# design.net
KiCad netlist of a schematic drawn in EasyEDA Pro
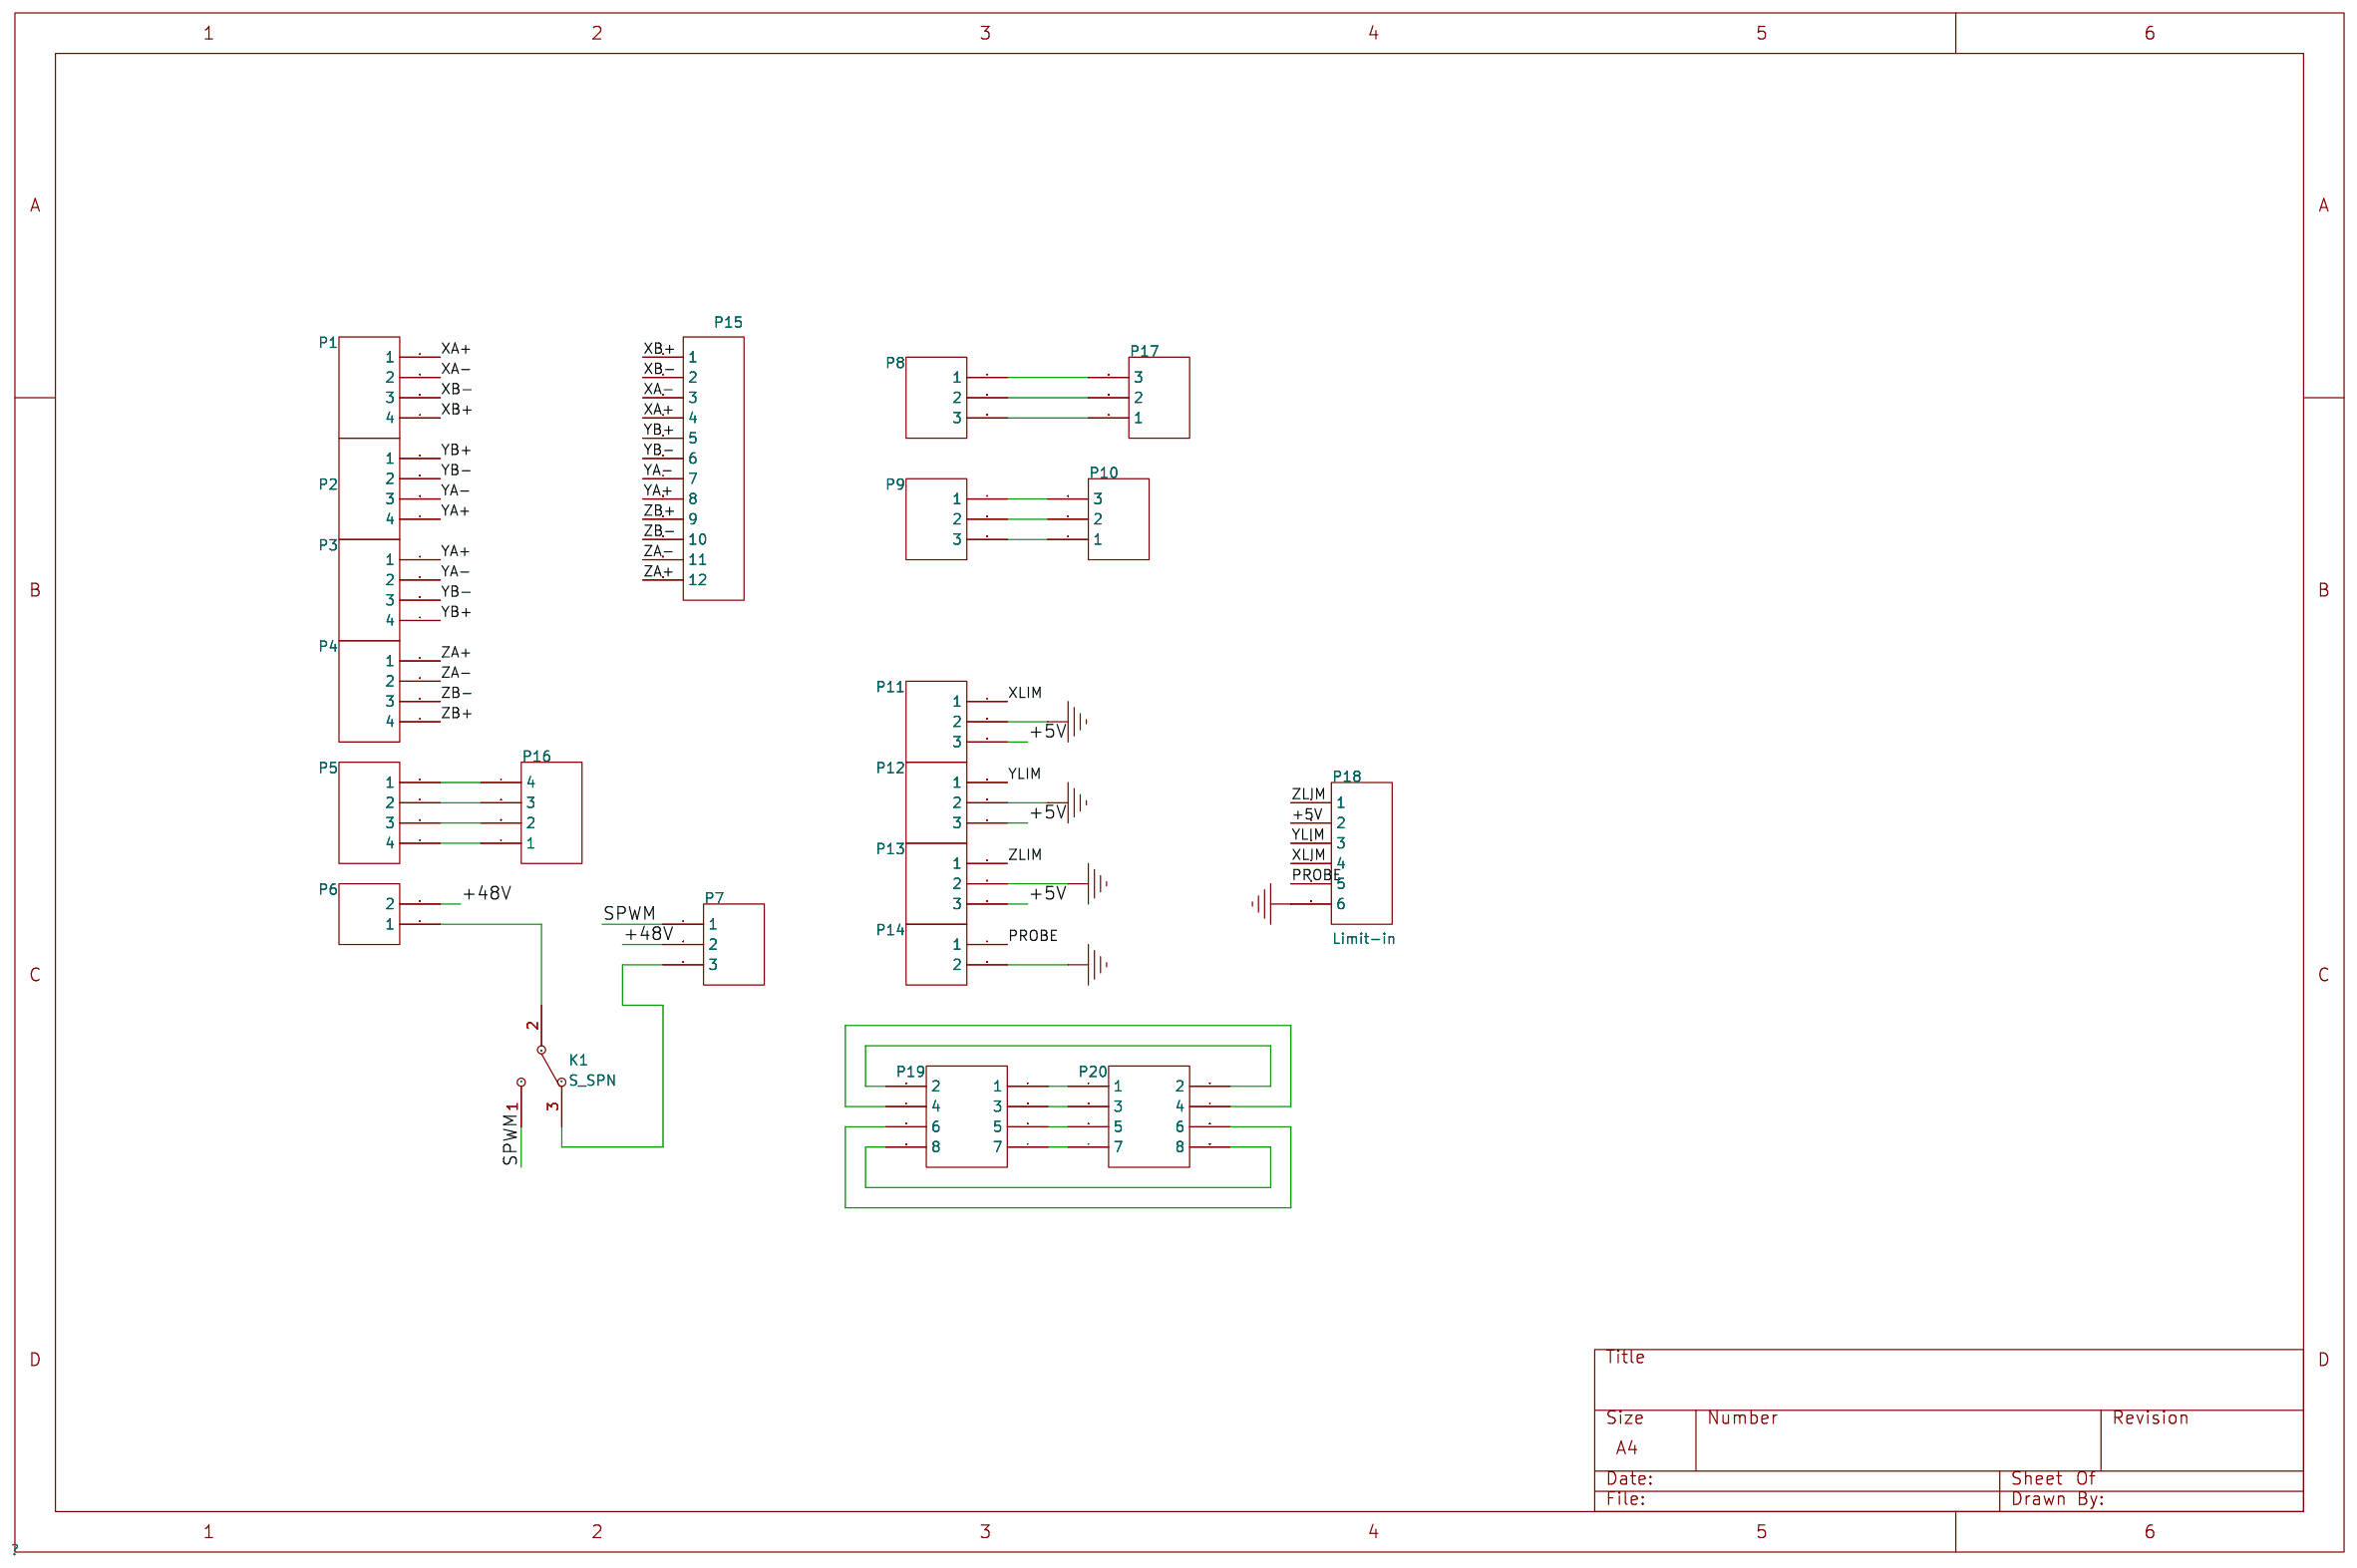
[diagram p0: schematic sheet]

(export (version "E")
  (design (tool "Eeschema 10.0.6"))
  (components
    (comp (ref "K1")
      (value "S_SPN")
      (footprint "easyedapro:SW-TH_SS-12D10L3")
      (description "SS-12D10L5")
      (fields (field (name "Publisher") "Altium Limited"))
      (libsource (lib "easyedapro") (part "SW-SPDT"))
    )
    (comp (ref "P1")
      (value "X-out")
      (footprint "easyedapro:HDR1X4_CON")
      (description "KF2EDGVC-5.0-4P，直插")
      (fields (field (name "Publisher") "Altium Limited"))
      (libsource (lib "easyedapro") (part "Header 4H"))
    )
    (comp (ref "P2")
      (value "Y1-out")
      (footprint "easyedapro:HDR1X4_CON")
      (description "KF2EDGVC-5.0-4P，直插")
      (fields (field (name "Publisher") "Altium Limited"))
      (libsource (lib "easyedapro") (part "Header 4H"))
    )
    (comp (ref "P3")
      (value "Y2-out")
      (footprint "easyedapro:HDR1X4_CON")
      (description "KF2EDGVC-5.0-4P，直插")
      (fields (field (name "Publisher") "Altium Limited"))
      (libsource (lib "easyedapro") (part "Header 4H"))
    )
    (comp (ref "P4")
      (value "Z-out")
      (footprint "easyedapro:HDR1X4_CON")
      (description "KF2EDGVC-5.0-4P，直插")
      (fields (field (name "Publisher") "Altium Limited"))
      (libsource (lib "easyedapro") (part "Header 4H"))
    )
    (comp (ref "P5")
      (value "Aout")
      (footprint "easyedapro:HDR1X4_CON")
      (description "KF2EDGVC-5.0-4P，直插")
      (fields (field (name "Publisher") "Altium Limited"))
      (libsource (lib "easyedapro") (part "Header 4H"))
    )
    (comp (ref "P6")
      (value "SPN-out")
      (footprint "easyedapro:CONN-TH_2P-P5.00_KF2EDGVC-5.08-2P")
      (description "KF2EDGVC-5.0-2P，直插")
      (fields (field (name "Publisher") "Altium Limited"))
      (libsource (lib "easyedapro") (part "Header 2H"))
    )
    (comp (ref "P7")
      (value "SPN-in")
      (footprint "easyedapro:CONN-TH_3P-P5.00_KF2EDGVC-5.08-3P")
      (description "KF2EDGVC-5.0-3P，直插")
      (fields (field (name "Publisher") "Altium Limited"))
      (libsource (lib "easyedapro") (part "Header 3H"))
    )
    (comp (ref "P8")
      (value "Laser-out")
      (footprint "easyedapro:CONN-TH_3P-P5.00_KF2EDGVC-5.08-3P")
      (description "KF2EDGVC-5.0-3P，直插")
      (fields (field (name "Publisher") "Altium Limited"))
      (libsource (lib "easyedapro") (part "Header 3H"))
    )
    (comp (ref "P9")
      (value "BL-out")
      (footprint "easyedapro:CONN-TH_3P-P5.00_KF2EDGVC-5.08-3P")
      (description "KF2EDGVC-5.0-3P，直插")
      (fields (field (name "Publisher") "Altium Limited"))
      (libsource (lib "easyedapro") (part "Header 3H"))
    )
    (comp (ref "P10")
      (value "BL-in")
      (footprint "easyedapro:CONN-TH_3P-P5.00_KF2EDGVC-5.08-3P")
      (description "KF2EDGVC-5.0-3P，直插")
      (fields (field (name "Publisher") "Altium Limited"))
      (libsource (lib "easyedapro") (part "Header 3H"))
    )
    (comp (ref "P11")
      (value "XLimt-out")
      (footprint "easyedapro:CONN-TH_3P-P5.00_KF2EDGVC-5.08-3P")
      (description "KF2EDGVC-5.0-3P，直插")
      (fields (field (name "Publisher") "Altium Limited"))
      (libsource (lib "easyedapro") (part "Header 3H"))
    )
    (comp (ref "P12")
      (value "YLimt-out")
      (footprint "easyedapro:CONN-TH_3P-P5.00_KF2EDGVC-5.08-3P")
      (description "KF2EDGVC-5.0-3P，直插")
      (fields (field (name "Publisher") "Altium Limited"))
      (libsource (lib "easyedapro") (part "Header 3H"))
    )
    (comp (ref "P13")
      (value "ZLimt-out")
      (footprint "easyedapro:CONN-TH_3P-P5.00_KF2EDGVC-5.08-3P")
      (description "KF2EDGVC-5.0-3P，直插")
      (fields (field (name "Publisher") "Altium Limited"))
      (libsource (lib "easyedapro") (part "Header 3H"))
    )
    (comp (ref "P14")
      (value "Probe-out")
      (footprint "easyedapro:CONN-TH_2P-P5.00_KF2EDGVC-5.08-2P")
      (description "Header, 2-Pin, Right Angle")
      (fields (field (name "Publisher") "Altium Limited"))
      (libsource (lib "easyedapro") (part "Header 2H"))
    )
    (comp (ref "P15")
      (value "XYZAxis")
      (footprint "easyedapro:HDR1X12_CON")
      (description "2.54立式直插12P")
      (fields (field (name "Publisher") "Altium Limited"))
      (libsource (lib "easyedapro") (part "Header 12H"))
    )
    (comp (ref "P16")
      (value "Ain")
      (footprint "easyedapro:HDR1X4_CON")
      (description "2.54立式直插4P")
      (fields (field (name "Publisher") "Altium Limited"))
      (libsource (lib "easyedapro") (part "Header 4H"))
    )
    (comp (ref "P17")
      (value "Laser-in")
      (footprint "easyedapro:CONN-TH_3P-P5.00_KF2EDGVC-5.08-3P")
      (description "2.54立式直插3P")
      (fields (field (name "Publisher") "Altium Limited"))
      (libsource (lib "easyedapro") (part "Header 3H"))
    )
    (comp (ref "P18")
      (value "Limit-in")
      (footprint "easyedapro:HDR1X6_CON")
      (description "2.54立式直插6P")
      (fields (field (name "Publisher") "Altium Limited"))
      (libsource (lib "easyedapro") (part "Header 6"))
    )
    (comp (ref "P19")
      (value "Offline-out")
      (footprint "easyedapro:IDC-TH_MTB110-08S - duplicate")
      (description "IDC连接器（牛角/简牛）2x4P")
      (fields (field (name "Publisher") "Altium Limited"))
      (libsource (lib "easyedapro") (part "MHDR2X4"))
    )
    (comp (ref "P20")
      (value "Offline-in")
      (footprint "easyedapro:IDC-TH_MTB110-08S - duplicate")
      (description "IDC连接器（牛角/简牛）2x4P")
      (fields (field (name "Publisher") "Altium Limited"))
      (libsource (lib "easyedapro") (part "MHDR2X4"))
    )
  )
  (nets
    (net (code "1") (name "/+5V") (class "Default")
      (node (ref "P11") (pin "3") (pinfunction "3_3") (pintype "unspecified"))
      (node (ref "P12") (pin "3") (pinfunction "3_3") (pintype "unspecified"))
      (node (ref "P13") (pin "3") (pinfunction "3_3") (pintype "unspecified"))
      (node (ref "P18") (pin "2") (pinfunction "2_2") (pintype "unspecified"))
    )
    (net (code "2") (name "/+48V") (class "Default")
      (node (ref "P6") (pin "2") (pinfunction "2_2") (pintype "unspecified"))
      (node (ref "P7") (pin "2") (pinfunction "2_2") (pintype "unspecified"))
    )
    (net (code "3") (name "/PROBE") (class "Default")
      (node (ref "P14") (pin "1") (pinfunction "1_1") (pintype "unspecified"))
      (node (ref "P18") (pin "5") (pinfunction "5_5") (pintype "unspecified"))
    )
    (net (code "4") (name "/SPWM") (class "Default")
      (node (ref "K1") (pin "1") (pinfunction "1_1") (pintype "unspecified"))
      (node (ref "P7") (pin "1") (pinfunction "1_1") (pintype "unspecified"))
    )
    (net (code "5") (name "/XA+") (class "Default")
      (node (ref "P1") (pin "1") (pinfunction "1_1") (pintype "unspecified"))
      (node (ref "P15") (pin "4") (pinfunction "4_4") (pintype "unspecified"))
    )
    (net (code "6") (name "/XA-") (class "Default")
      (node (ref "P1") (pin "2") (pinfunction "2_2") (pintype "unspecified"))
      (node (ref "P15") (pin "3") (pinfunction "3_3") (pintype "unspecified"))
    )
    (net (code "7") (name "/XB+") (class "Default")
      (node (ref "P1") (pin "4") (pinfunction "4_4") (pintype "unspecified"))
      (node (ref "P15") (pin "1") (pinfunction "1_1") (pintype "unspecified"))
    )
    (net (code "8") (name "/XB-") (class "Default")
      (node (ref "P1") (pin "3") (pinfunction "3_3") (pintype "unspecified"))
      (node (ref "P15") (pin "2") (pinfunction "2_2") (pintype "unspecified"))
    )
    (net (code "9") (name "/XLIM") (class "Default")
      (node (ref "P11") (pin "1") (pinfunction "1_1") (pintype "unspecified"))
      (node (ref "P18") (pin "4") (pinfunction "4_4") (pintype "unspecified"))
    )
    (net (code "10") (name "/YA+") (class "Default")
      (node (ref "P15") (pin "8") (pinfunction "8_8") (pintype "unspecified"))
      (node (ref "P2") (pin "4") (pinfunction "4_4") (pintype "unspecified"))
      (node (ref "P3") (pin "1") (pinfunction "1_1") (pintype "unspecified"))
    )
    (net (code "11") (name "/YA-") (class "Default")
      (node (ref "P15") (pin "7") (pinfunction "7_7") (pintype "unspecified"))
      (node (ref "P2") (pin "3") (pinfunction "3_3") (pintype "unspecified"))
      (node (ref "P3") (pin "2") (pinfunction "2_2") (pintype "unspecified"))
    )
    (net (code "12") (name "/YB+") (class "Default")
      (node (ref "P15") (pin "5") (pinfunction "5_5") (pintype "unspecified"))
      (node (ref "P2") (pin "1") (pinfunction "1_1") (pintype "unspecified"))
      (node (ref "P3") (pin "4") (pinfunction "4_4") (pintype "unspecified"))
    )
    (net (code "13") (name "/YB-") (class "Default")
      (node (ref "P15") (pin "6") (pinfunction "6_6") (pintype "unspecified"))
      (node (ref "P2") (pin "2") (pinfunction "2_2") (pintype "unspecified"))
      (node (ref "P3") (pin "3") (pinfunction "3_3") (pintype "unspecified"))
    )
    (net (code "14") (name "/YLIM") (class "Default")
      (node (ref "P12") (pin "1") (pinfunction "1_1") (pintype "unspecified"))
      (node (ref "P18") (pin "3") (pinfunction "3_3") (pintype "unspecified"))
    )
    (net (code "15") (name "/ZA+") (class "Default")
      (node (ref "P15") (pin "12") (pinfunction "12_12") (pintype "unspecified"))
      (node (ref "P4") (pin "1") (pinfunction "1_1") (pintype "unspecified"))
    )
    (net (code "16") (name "/ZA-") (class "Default")
      (node (ref "P15") (pin "11") (pinfunction "11_11") (pintype "unspecified"))
      (node (ref "P4") (pin "2") (pinfunction "2_2") (pintype "unspecified"))
    )
    (net (code "17") (name "/ZB+") (class "Default")
      (node (ref "P15") (pin "9") (pinfunction "9_9") (pintype "unspecified"))
      (node (ref "P4") (pin "4") (pinfunction "4_4") (pintype "unspecified"))
    )
    (net (code "18") (name "/ZB-") (class "Default")
      (node (ref "P15") (pin "10") (pinfunction "10_10") (pintype "unspecified"))
      (node (ref "P4") (pin "3") (pinfunction "3_3") (pintype "unspecified"))
    )
    (net (code "19") (name "/ZLIM") (class "Default")
      (node (ref "P13") (pin "1") (pinfunction "1_1") (pintype "unspecified"))
      (node (ref "P18") (pin "1") (pinfunction "1_1") (pintype "unspecified"))
    )
    (net (code "20") (name "GND") (class "Default")
      (node (ref "P11") (pin "2") (pinfunction "2_2") (pintype "unspecified"))
      (node (ref "P12") (pin "2") (pinfunction "2_2") (pintype "unspecified"))
      (node (ref "P13") (pin "2") (pinfunction "2_2") (pintype "unspecified"))
      (node (ref "P14") (pin "2") (pinfunction "2_2") (pintype "unspecified"))
      (node (ref "P18") (pin "6") (pinfunction "6_6") (pintype "unspecified"))
    )
    (net (code "21") (name "Net-(K1-Pad2)") (class "Default")
      (node (ref "K1") (pin "2") (pinfunction "2_2") (pintype "unspecified"))
      (node (ref "P6") (pin "1") (pinfunction "1_1") (pintype "unspecified"))
    )
    (net (code "22") (name "Net-(K1-Pad3)") (class "Default")
      (node (ref "K1") (pin "3") (pinfunction "3_3") (pintype "unspecified"))
      (node (ref "P7") (pin "3") (pinfunction "3_3") (pintype "unspecified"))
    )
    (net (code "23") (name "Net-(P10-Pad1)") (class "Default")
      (node (ref "P10") (pin "1") (pinfunction "1_1") (pintype "unspecified"))
      (node (ref "P9") (pin "3") (pinfunction "3_3") (pintype "unspecified"))
    )
    (net (code "24") (name "Net-(P10-Pad2)") (class "Default")
      (node (ref "P10") (pin "2") (pinfunction "2_2") (pintype "unspecified"))
      (node (ref "P9") (pin "2") (pinfunction "2_2") (pintype "unspecified"))
    )
    (net (code "25") (name "Net-(P10-Pad3)") (class "Default")
      (node (ref "P10") (pin "3") (pinfunction "3_3") (pintype "unspecified"))
      (node (ref "P9") (pin "1") (pinfunction "1_1") (pintype "unspecified"))
    )
    (net (code "26") (name "Net-(P16-Pad1)") (class "Default")
      (node (ref "P16") (pin "1") (pinfunction "1_1") (pintype "unspecified"))
      (node (ref "P5") (pin "4") (pinfunction "4_4") (pintype "unspecified"))
    )
    (net (code "27") (name "Net-(P16-Pad2)") (class "Default")
      (node (ref "P16") (pin "2") (pinfunction "2_2") (pintype "unspecified"))
      (node (ref "P5") (pin "3") (pinfunction "3_3") (pintype "unspecified"))
    )
    (net (code "28") (name "Net-(P16-Pad3)") (class "Default")
      (node (ref "P16") (pin "3") (pinfunction "3_3") (pintype "unspecified"))
      (node (ref "P5") (pin "2") (pinfunction "2_2") (pintype "unspecified"))
    )
    (net (code "29") (name "Net-(P16-Pad4)") (class "Default")
      (node (ref "P16") (pin "4") (pinfunction "4_4") (pintype "unspecified"))
      (node (ref "P5") (pin "1") (pinfunction "1_1") (pintype "unspecified"))
    )
    (net (code "30") (name "Net-(P17-Pad1)") (class "Default")
      (node (ref "P17") (pin "1") (pinfunction "1_1") (pintype "unspecified"))
      (node (ref "P8") (pin "3") (pinfunction "3_3") (pintype "unspecified"))
    )
    (net (code "31") (name "Net-(P17-Pad2)") (class "Default")
      (node (ref "P17") (pin "2") (pinfunction "2_2") (pintype "unspecified"))
      (node (ref "P8") (pin "2") (pinfunction "2_2") (pintype "unspecified"))
    )
    (net (code "32") (name "Net-(P17-Pad3)") (class "Default")
      (node (ref "P17") (pin "3") (pinfunction "3_3") (pintype "unspecified"))
      (node (ref "P8") (pin "1") (pinfunction "1_1") (pintype "unspecified"))
    )
    (net (code "33") (name "Net-(P19-Pad1)") (class "Default")
      (node (ref "P19") (pin "1") (pinfunction "1_1") (pintype "unspecified"))
      (node (ref "P20") (pin "1") (pinfunction "1_1") (pintype "unspecified"))
    )
    (net (code "34") (name "Net-(P19-Pad2)") (class "Default")
      (node (ref "P19") (pin "2") (pinfunction "2_2") (pintype "unspecified"))
      (node (ref "P20") (pin "2") (pinfunction "2_2") (pintype "unspecified"))
    )
    (net (code "35") (name "Net-(P19-Pad3)") (class "Default")
      (node (ref "P19") (pin "3") (pinfunction "3_3") (pintype "unspecified"))
      (node (ref "P20") (pin "3") (pinfunction "3_3") (pintype "unspecified"))
    )
    (net (code "36") (name "Net-(P19-Pad4)") (class "Default")
      (node (ref "P19") (pin "4") (pinfunction "4_4") (pintype "unspecified"))
      (node (ref "P20") (pin "4") (pinfunction "4_4") (pintype "unspecified"))
    )
    (net (code "37") (name "Net-(P19-Pad5)") (class "Default")
      (node (ref "P19") (pin "5") (pinfunction "5_5") (pintype "unspecified"))
      (node (ref "P20") (pin "5") (pinfunction "5_5") (pintype "unspecified"))
    )
    (net (code "38") (name "Net-(P19-Pad6)") (class "Default")
      (node (ref "P19") (pin "6") (pinfunction "6_6") (pintype "unspecified"))
      (node (ref "P20") (pin "6") (pinfunction "6_6") (pintype "unspecified"))
    )
    (net (code "39") (name "Net-(P19-Pad7)") (class "Default")
      (node (ref "P19") (pin "7") (pinfunction "7_7") (pintype "unspecified"))
      (node (ref "P20") (pin "7") (pinfunction "7_7") (pintype "unspecified"))
    )
    (net (code "40") (name "Net-(P19-Pad8)") (class "Default")
      (node (ref "P19") (pin "8") (pinfunction "8_8") (pintype "unspecified"))
      (node (ref "P20") (pin "8") (pinfunction "8_8") (pintype "unspecified"))
    )
  )
)
